# main.net
KiCad netlist of a schematic drawn in Altium Designer
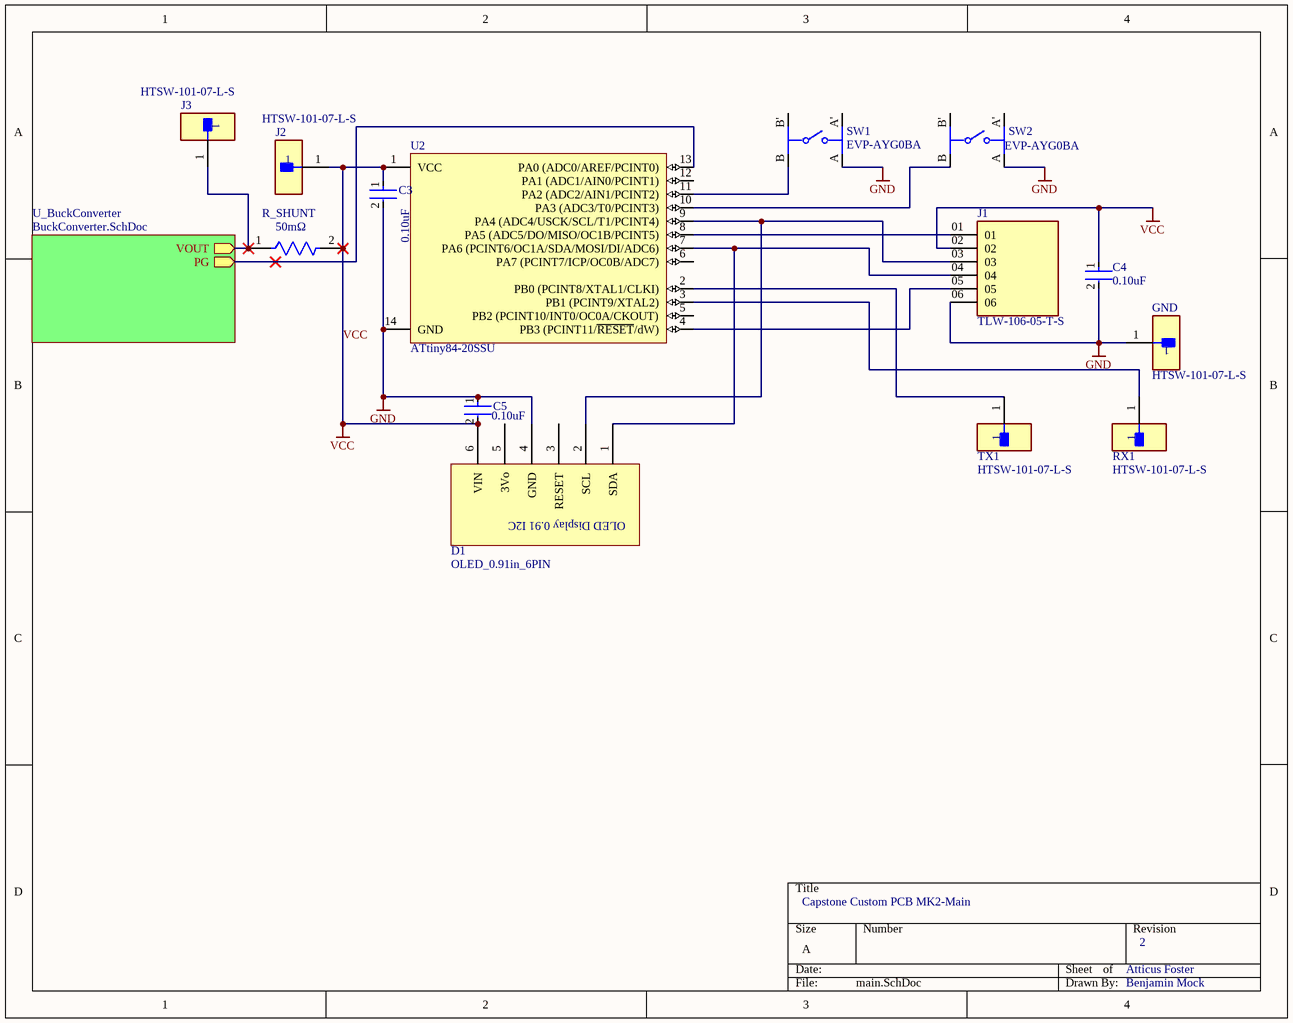
[diagram p0: main.SchDoc]

(export (version "E")
  (design (tool "Eeschema 10.0.6"))
  (components
    (comp (ref "C3")
      (value "0.10uF")
      (footprint "FP-GRM155-0_05-MFG")
      (description "Chip Multilayer Ceramic Capacitors for General Purpose, 0402, 0.10uF, X7S, 22%, 10%, 50V")
      (fields (field (name "TOLERANCE") "10%"))
      (libsource (lib "Altium Content Vault") (part "02cd4be3c70576c341d710602a673aa"))
    )
    (comp (ref "C4")
      (value "0.10uF")
      (footprint "FP-GRM155-0_05-MFG")
      (description "Chip Multilayer Ceramic Capacitors for General Purpose, 0402, 0.10uF, X7S, 22%, 10%, 50V")
      (fields (field (name "TOLERANCE") "10%"))
      (libsource (lib "Altium Content Vault") (part "02cd4be3c70576c341d710602a673aa"))
    )
    (comp (ref "C5")
      (value "0.10uF")
      (footprint "FP-GRM155-0_05-MFG")
      (description "Chip Multilayer Ceramic Capacitors for General Purpose, 0402, 0.10uF, X7S, 22%, 10%, 50V")
      (fields (field (name "TOLERANCE") "10%"))
      (libsource (lib "Altium Content Vault") (part "02cd4be3c70576c341d710602a673aa"))
    )
    (comp (ref "D1")
      (value "OLED_0.91in_6PIN")
      (footprint "PCBComponent_1")
      (libsource (lib "OLED_Display") (part "OLED_0.91in_6PIN"))
    )
    (comp (ref "GND")
      (value "HTSW-101-07-L-S")
      (footprint "FP-HTSW-101-07-L-S-MFG")
      (description "CONN HEADER VERT 1POS")
      (libsource (lib "") (part "dd45045ce8184df9e99e12baf3f412c_3"))
    )
    (comp (ref "J1")
      (value "TLW-106-05-T-S")
      (footprint "SAMTEC_TLW-106-05-T-S")
      (libsource (lib "TLW-106-05-T-S") (part "TLW-106-05-T-S"))
    )
    (comp (ref "J2")
      (value "HTSW-101-07-L-S")
      (footprint "FP-HTSW-101-07-L-S-MFG")
      (description "CONN HEADER VERT 1POS")
      (libsource (lib "") (part "dd45045ce8184df9e99e12baf3f412c_1"))
    )
    (comp (ref "J3")
      (value "HTSW-101-07-L-S")
      (footprint "FP-HTSW-101-07-L-S-MFG")
      (description "CONN HEADER VERT 1POS")
      (libsource (lib "") (part "dd45045ce8184df9e99e12baf3f412c_2"))
    )
    (comp (ref "RX1")
      (value "HTSW-101-07-L-S")
      (footprint "FP-HTSW-101-07-L-S-MFG")
      (description "CONN HEADER VERT 1POS")
      (libsource (lib "Altium Content Vault") (part "dd45045ce8184df9e99e12baf3f412c"))
    )
    (comp (ref "R_SHUNT")
      (value "50mΩ")
      (footprint "FP-CSRN2512-IPC_B")
      (description "Res Thick Film 2512 50mΩ 1% 2W ±200ppm/°C Molded SMD Plastic T/R")
      (fields (field (name "TOLERANCE") "1%"))
      (libsource (lib "Altium Content Vault") (part "1029c3af85768c4190bb7ad29bc67b5"))
    )
    (comp (ref "SW1")
      (value "EVP-AYG0BA")
      (footprint "FP-EVP-AYG0BA-MFG")
      (description "SWITCH TACTILE SPST-NO 0.02A 15V")
      (libsource (lib "Altium Content Vault") (part "ac634b74112f77252d8361be3a8fb16"))
    )
    (comp (ref "SW2")
      (value "EVP-AYG0BA")
      (footprint "FP-EVP-AYG0BA-MFG")
      (description "SWITCH TACTILE SPST-NO 0.02A 15V")
      (libsource (lib "Altium Content Vault") (part "ac634b74112f77252d8361be3a8fb16"))
    )
    (comp (ref "TX1")
      (value "HTSW-101-07-L-S")
      (footprint "FP-HTSW-101-07-L-S-MFG")
      (description "CONN HEADER VERT 1POS")
      (libsource (lib "Altium Content Vault") (part "dd45045ce8184df9e99e12baf3f412c"))
    )
    (comp (ref "U2")
      (value "ATtiny84-20SSU")
      (footprint "14S1_N")
      (libsource (lib "Altium Content Vault") (part "MC-8B-ATTINY24V-IL14"))
    )
  )
  (nets
    (net (code "1") (name "/PG") (class "Default")
      (node (ref "U2") (pin "13") (pinfunction "PA0_(ADC0/AREF/PCINT0)_13") (pintype "bidirectional"))
    )
    (net (code "2") (name "/VOUT") (class "Default")
      (node (ref "J3") (pin "1") (pinfunction "1_1") (pintype "passive"))
      (node (ref "R_SHUNT") (pin "1") (pinfunction "1_1") (pintype "passive"))
    )
    (net (code "3") (name "GND") (class "Default")
      (node (ref "C3") (pin "2") (pinfunction "2_2") (pintype "passive"))
      (node (ref "C4") (pin "2") (pinfunction "2_2") (pintype "passive"))
      (node (ref "C5") (pin "1") (pinfunction "1_1") (pintype "passive"))
      (node (ref "D1") (pin "4") (pinfunction "GND_4") (pintype "passive"))
      (node (ref "GND") (pin "1") (pinfunction "1_1") (pintype "passive"))
      (node (ref "J1") (pin "06") (pinfunction "06_06") (pintype "passive"))
      (node (ref "SW1") (pin "A") (pinfunction "A_A") (pintype "passive"))
      (node (ref "SW2") (pin "A") (pinfunction "A_A") (pintype "passive"))
      (node (ref "U2") (pin "14") (pinfunction "GND_14") (pintype "power_in"))
    )
    (net (code "4") (name "Net-(D1-SCL)") (class "Default")
      (node (ref "D1") (pin "2") (pinfunction "SCL_2") (pintype "passive"))
      (node (ref "J1") (pin "03") (pinfunction "03_03") (pintype "passive"))
      (node (ref "U2") (pin "9") (pinfunction "PA4_(ADC4/USCK/SCL/T1/PCINT4)_9") (pintype "bidirectional"))
    )
    (net (code "5") (name "Net-(D1-SDA)") (class "Default")
      (node (ref "D1") (pin "1") (pinfunction "SDA_1") (pintype "passive"))
      (node (ref "J1") (pin "04") (pinfunction "04_04") (pintype "passive"))
      (node (ref "U2") (pin "7") (pinfunction "PA6_(PCINT6/OC1A/SDA/MOSI/DI/ADC6)_7") (pintype "bidirectional"))
    )
    (net (code "6") (name "Net-(U2-PA2_(ADC2{slash}AIN1{slash}PCINT2))") (class "Default")
      (node (ref "SW1") (pin "B") (pinfunction "B_B") (pintype "passive"))
      (node (ref "U2") (pin "11") (pinfunction "PA2_(ADC2/AIN1/PCINT2)_11") (pintype "bidirectional"))
    )
    (net (code "7") (name "Net-(U2-PA3_(ADC3{slash}T0{slash}PCINT3))") (class "Default")
      (node (ref "SW2") (pin "B") (pinfunction "B_B") (pintype "passive"))
      (node (ref "U2") (pin "10") (pinfunction "PA3_(ADC3/T0/PCINT3)_10") (pintype "bidirectional"))
    )
    (net (code "8") (name "Net-(U2-PA5_(ADC5{slash}DO{slash}MISO{slash}OC1B{slash}PCINT5))") (class "Default")
      (node (ref "J1") (pin "01") (pinfunction "01_01") (pintype "passive"))
      (node (ref "U2") (pin "8") (pinfunction "PA5_(ADC5/DO/MISO/OC1B/PCINT5)_8") (pintype "bidirectional"))
    )
    (net (code "9") (name "Net-(U2-PB0_(PCINT8{slash}XTAL1{slash}CLKI))") (class "Default")
      (node (ref "TX1") (pin "1") (pinfunction "1_1") (pintype "passive"))
      (node (ref "U2") (pin "2") (pinfunction "PB0_(PCINT8/XTAL1/CLKI)_2") (pintype "bidirectional"))
    )
    (net (code "10") (name "Net-(U2-PB1_(PCINT9{slash}XTAL2))") (class "Default")
      (node (ref "RX1") (pin "1") (pinfunction "1_1") (pintype "passive"))
      (node (ref "U2") (pin "3") (pinfunction "PB1_(PCINT9/XTAL2)_3") (pintype "bidirectional"))
    )
    (net (code "11") (name "Net-(U2-PB3_(PCINT11{slash}~{RESET}{slash}dW))") (class "Default")
      (node (ref "J1") (pin "05") (pinfunction "05_05") (pintype "passive"))
      (node (ref "U2") (pin "4") (pinfunction "PB3_(PCINT11/~{RESET}/dW)_4") (pintype "bidirectional"))
    )
    (net (code "12") (name "VCC") (class "Default")
      (node (ref "C3") (pin "1") (pinfunction "1_1") (pintype "passive"))
      (node (ref "C4") (pin "1") (pinfunction "1_1") (pintype "passive"))
      (node (ref "C5") (pin "2") (pinfunction "2_2") (pintype "passive"))
      (node (ref "D1") (pin "6") (pinfunction "VIN_6") (pintype "passive"))
      (node (ref "J1") (pin "02") (pinfunction "02_02") (pintype "passive"))
      (node (ref "J2") (pin "1") (pinfunction "1_1") (pintype "passive"))
      (node (ref "R_SHUNT") (pin "2") (pinfunction "2_2") (pintype "passive"))
      (node (ref "U2") (pin "1") (pinfunction "VCC_1") (pintype "power_in"))
    )
    (net (code "13") (name "unconnected-(D1-3Vo-Pad5)") (class "Default")
      (node (ref "D1") (pin "5") (pinfunction "3Vo_5") (pintype "passive"))
    )
    (net (code "14") (name "unconnected-(D1-RESET-Pad3)") (class "Default")
      (node (ref "D1") (pin "3") (pinfunction "RESET_3") (pintype "passive"))
    )
    (net (code "15") (name "unconnected-(SW1-PadA')") (class "Default")
      (node (ref "SW1") (pin "A'") (pinfunction "A'_A'") (pintype "passive"))
    )
    (net (code "16") (name "unconnected-(SW1-PadB')") (class "Default")
      (node (ref "SW1") (pin "B'") (pinfunction "B'_B'") (pintype "passive"))
    )
    (net (code "17") (name "unconnected-(SW2-PadA')") (class "Default")
      (node (ref "SW2") (pin "A'") (pinfunction "A'_A'") (pintype "passive"))
    )
    (net (code "18") (name "unconnected-(SW2-PadB')") (class "Default")
      (node (ref "SW2") (pin "B'") (pinfunction "B'_B'") (pintype "passive"))
    )
    (net (code "19") (name "unconnected-(U2-PA1_(ADC1{slash}AIN0{slash}PCINT1)-Pad12)") (class "Default")
      (node (ref "U2") (pin "12") (pinfunction "PA1_(ADC1/AIN0/PCINT1)_12") (pintype "bidirectional"))
    )
    (net (code "20") (name "unconnected-(U2-PA7_(PCINT7{slash}ICP{slash}OC0B{slash}ADC7)-Pad6)") (class "Default")
      (node (ref "U2") (pin "6") (pinfunction "PA7_(PCINT7/ICP/OC0B/ADC7)_6") (pintype "bidirectional"))
    )
    (net (code "21") (name "unconnected-(U2-PB2_(PCINT10{slash}INT0{slash}OC0A{slash}CKOUT)-Pad5)") (class "Default")
      (node (ref "U2") (pin "5") (pinfunction "PB2_(PCINT10/INT0/OC0A/CKOUT)_5") (pintype "bidirectional"))
    )
  )
)
